# accel_sensor.net
KiCad netlist of a schematic drawn in EAGLE
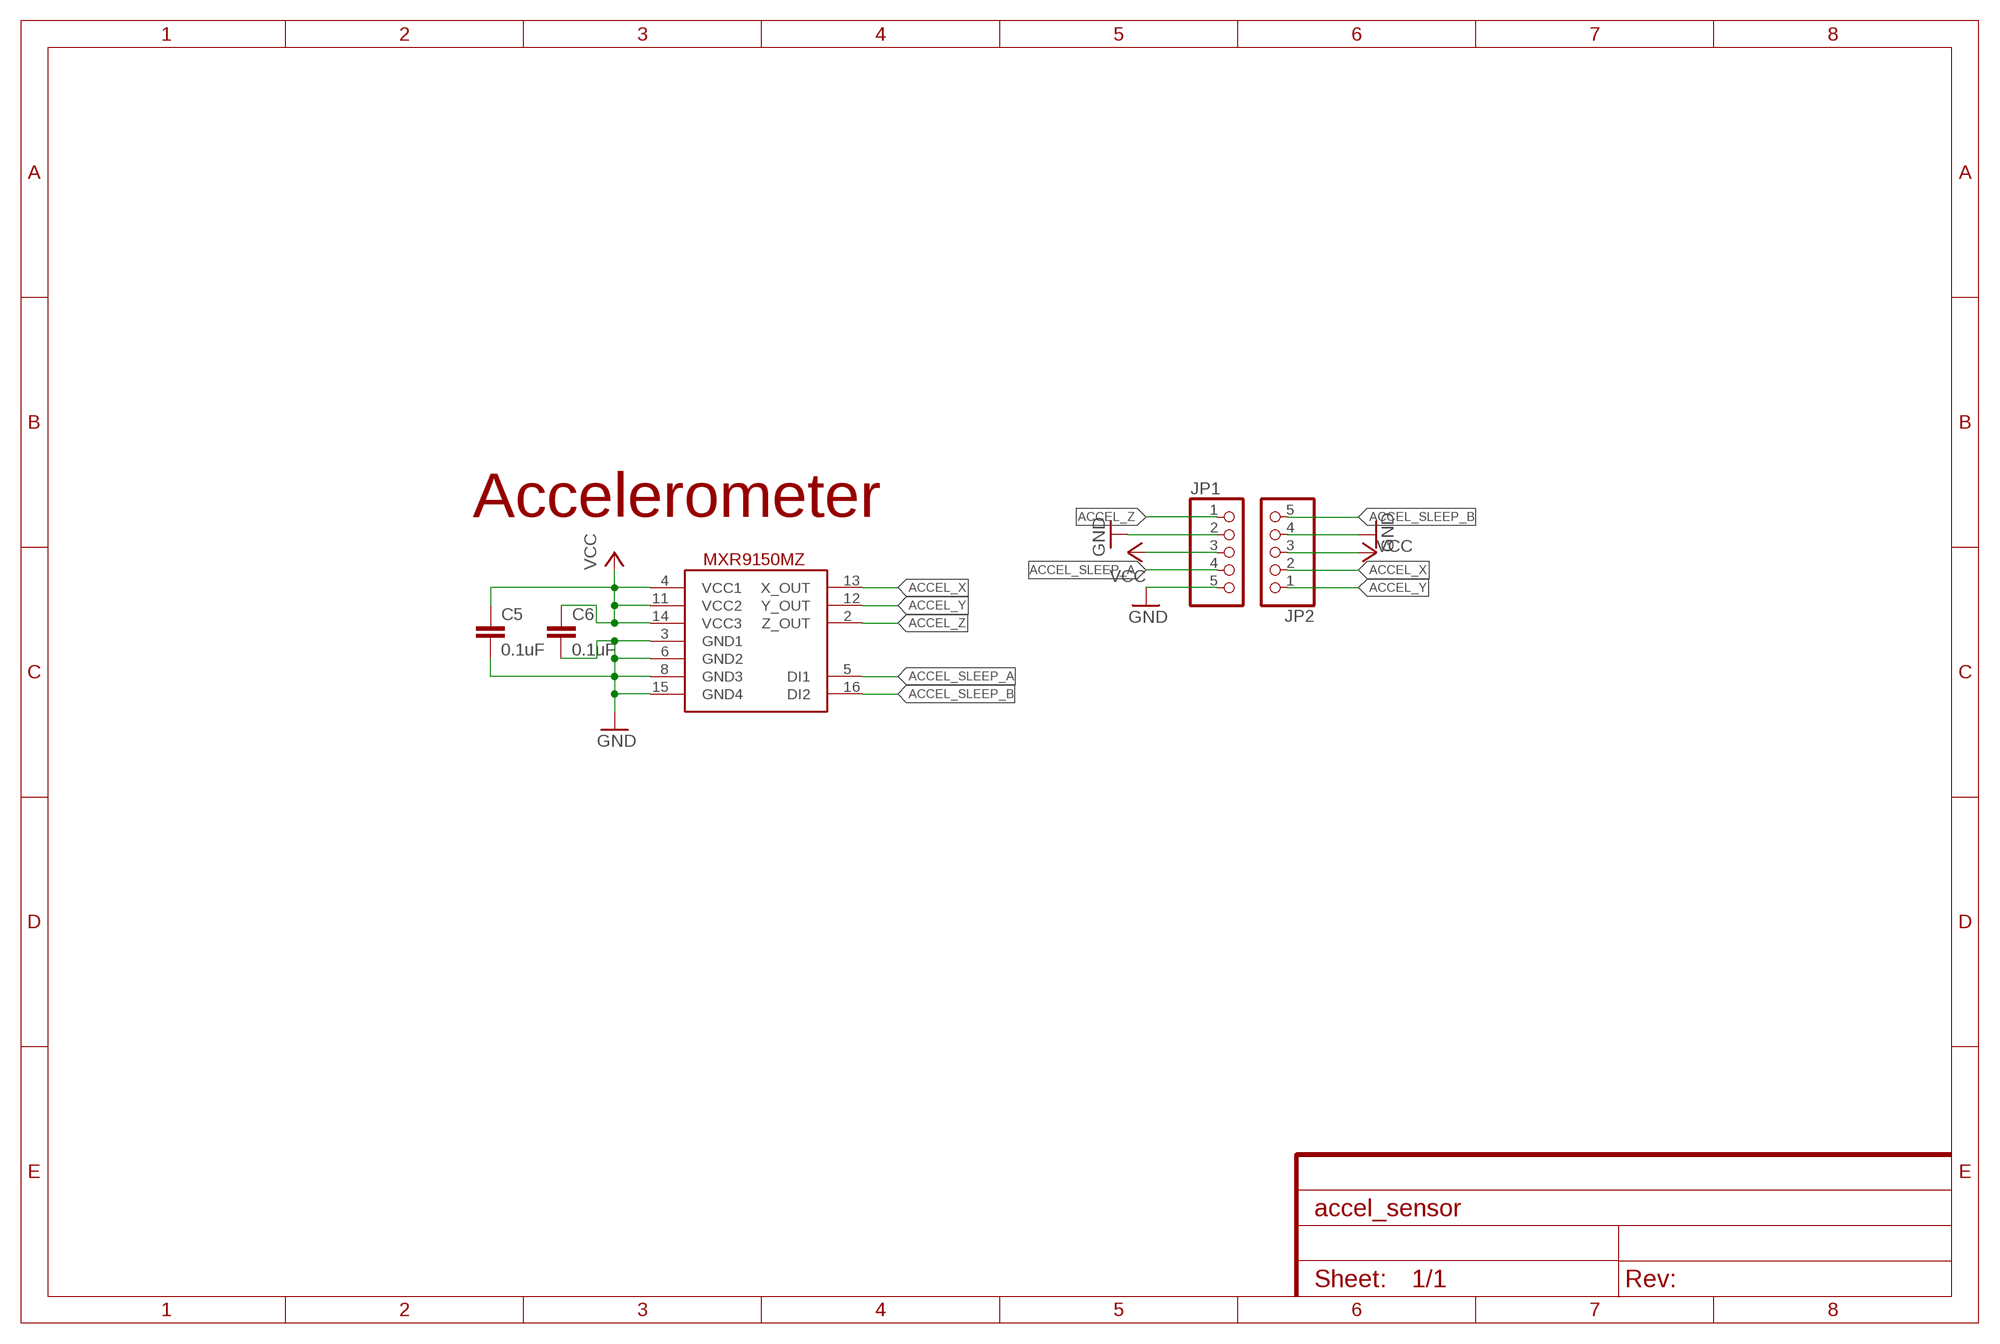
[diagram p0: schematic, sheet 1]

(export (version "E")
  (design (tool "Eeschema 10.0.6"))
  (components
    (comp (ref "C5")
      (value "0.1uF")
      (footprint "eagle-import:0402-CAP")
      (libsource (lib "eagle-import") (part "CAP0402-CAP"))
    )
    (comp (ref "C6")
      (value "0.1uF")
      (footprint "eagle-import:0402-CAP")
      (libsource (lib "eagle-import") (part "CAP0402-CAP"))
    )
    (comp (ref "JP1")
      (value "PINHD-1X5")
      (footprint "eagle-import:1X05")
      (libsource (lib "eagle-import") (part "PINHD-1X5"))
    )
    (comp (ref "JP2")
      (value "PINHD-1X5")
      (footprint "eagle-import:1X05")
      (libsource (lib "eagle-import") (part "PINHD-1X5"))
    )
    (comp (ref "U$1")
      (value "ACCELEROMETER_MXR9150MZ")
      (footprint "eagle-import:MXR9150MZ")
      (libsource (lib "eagle-import") (part "ACCELEROMETER_MXR9150MZ"))
    )
  )
  (nets
    (net (code "1") (name "ACCEL_SLEEP_A") (class "Default")
      (node (ref "JP1") (pin "4") (pinfunction "4_4") (pintype "passive"))
      (node (ref "U$1") (pin "5") (pinfunction "DI1_5") (pintype "bidirectional"))
    )
    (net (code "2") (name "ACCEL_SLEEP_B") (class "Default")
      (node (ref "JP2") (pin "5") (pinfunction "5_5") (pintype "passive"))
      (node (ref "U$1") (pin "16") (pinfunction "DI2_16") (pintype "bidirectional"))
    )
    (net (code "3") (name "ACCEL_X") (class "Default")
      (node (ref "JP2") (pin "2") (pinfunction "2_2") (pintype "passive"))
      (node (ref "U$1") (pin "13") (pinfunction "X_OUT_13") (pintype "bidirectional"))
    )
    (net (code "4") (name "ACCEL_Y") (class "Default")
      (node (ref "JP2") (pin "1") (pinfunction "1_1") (pintype "passive"))
      (node (ref "U$1") (pin "12") (pinfunction "Y_OUT_12") (pintype "bidirectional"))
    )
    (net (code "5") (name "ACCEL_Z") (class "Default")
      (node (ref "JP1") (pin "1") (pinfunction "1_1") (pintype "passive"))
      (node (ref "U$1") (pin "2") (pinfunction "Z_OUT_2") (pintype "bidirectional"))
    )
    (net (code "6") (name "GND") (class "Default")
      (node (ref "C5") (pin "2") (pinfunction "2_2") (pintype "passive"))
      (node (ref "C6") (pin "2") (pinfunction "2_2") (pintype "passive"))
      (node (ref "JP1") (pin "2") (pinfunction "2_2") (pintype "passive"))
      (node (ref "JP1") (pin "5") (pinfunction "5_5") (pintype "passive"))
      (node (ref "JP2") (pin "4") (pinfunction "4_4") (pintype "passive"))
      (node (ref "U$1") (pin "15") (pinfunction "GND4_15") (pintype "bidirectional"))
      (node (ref "U$1") (pin "3") (pinfunction "GND1_3") (pintype "bidirectional"))
      (node (ref "U$1") (pin "6") (pinfunction "GND2_6") (pintype "bidirectional"))
      (node (ref "U$1") (pin "8") (pinfunction "GND3_8") (pintype "bidirectional"))
    )
    (net (code "7") (name "VCC") (class "Default")
      (node (ref "C5") (pin "1") (pinfunction "1_1") (pintype "passive"))
      (node (ref "C6") (pin "1") (pinfunction "1_1") (pintype "passive"))
      (node (ref "JP1") (pin "3") (pinfunction "3_3") (pintype "passive"))
      (node (ref "JP2") (pin "3") (pinfunction "3_3") (pintype "passive"))
      (node (ref "U$1") (pin "11") (pinfunction "VCC2_11") (pintype "bidirectional"))
      (node (ref "U$1") (pin "14") (pinfunction "VCC3_14") (pintype "bidirectional"))
      (node (ref "U$1") (pin "4") (pinfunction "VCC1_4") (pintype "bidirectional"))
    )
  )
)
